# Panel_Interface.net
KiCad netlist of a schematic drawn in Altium Designer
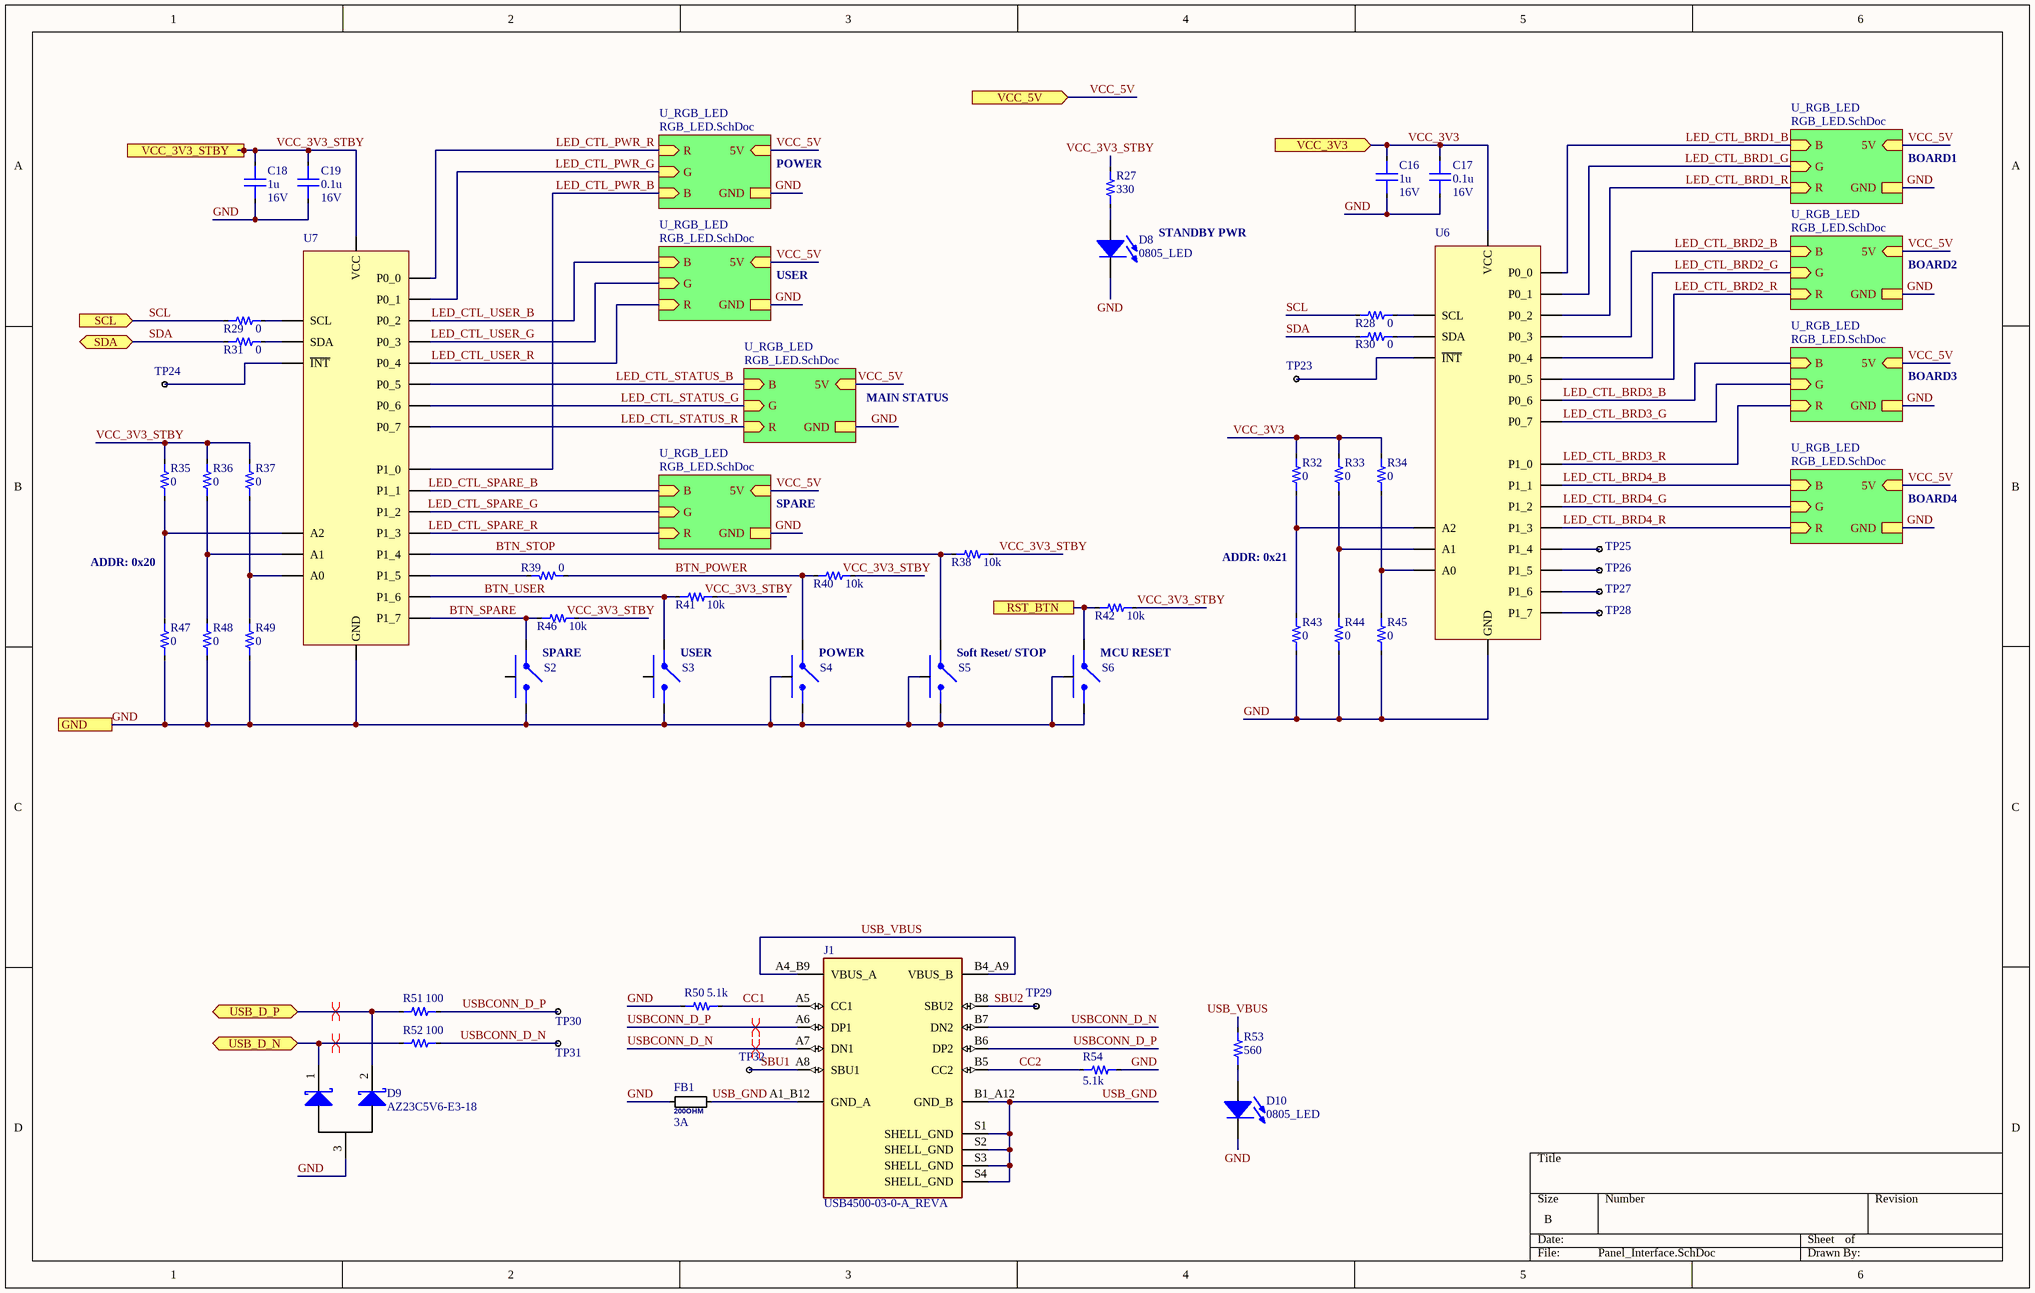
[diagram p0: Panel_Interface.SchDoc]

(export (version "E")
  (design (tool "Eeschema 10.0.6"))
  (components
    (comp (ref "C16")
      (value "1u")
      (footprint "0603_CAP")
      (fields (field (name "VOLTAGE") "16V") (field (name "Comment") "Capacitor"))
      (libsource (lib "Capacitors") (part "Capacitor"))
    )
    (comp (ref "C17")
      (value "0.1u")
      (footprint "0603_CAP")
      (fields (field (name "VOLTAGE") "16V") (field (name "Comment") "Capacitor"))
      (libsource (lib "Capacitors") (part "Capacitor"))
    )
    (comp (ref "C18")
      (value "1u")
      (footprint "0603_CAP")
      (fields (field (name "VOLTAGE") "16V") (field (name "Comment") "Capacitor"))
      (libsource (lib "Capacitors") (part "Capacitor"))
    )
    (comp (ref "C19")
      (value "0.1u")
      (footprint "0603_CAP")
      (fields (field (name "VOLTAGE") "16V") (field (name "Comment") "Capacitor"))
      (libsource (lib "Capacitors") (part "Capacitor"))
    )
    (comp (ref "D8")
      (value "0805_LED")
      (footprint "0805_LED")
      (description "Generic 0805 LED")
      (libsource (lib "Diodes") (part "0805_LED"))
    )
    (comp (ref "D9")
      (value "AZ23C5V6-E3-18")
      (footprint "SOT23-3")
      (description "Zener Diode Array 1 Pair Common Anode 5.6 V 300 mW ±7% SOT-23-3")
      (libsource (lib "Diodes") (part "AZ23C5V6-E3-18"))
    )
    (comp (ref "D10")
      (value "0805_LED")
      (footprint "0805_LED")
      (description "Generic 0805 LED")
      (libsource (lib "Diodes") (part "0805_LED"))
    )
    (comp (ref "FB1")
      (value "*")
      (footprint "0805_Ferrite")
      (fields (field (name "=Z@100MHZ") "200OHM") (field (name "IMAX") "3A"))
      (libsource (lib "Magnetic") (part "ChipFerrite"))
    )
    (comp (ref "J1")
      (value "USB4500-03-0-A_REVA")
      (footprint "GCT_USB4500-03-0-A_REVA")
      (description "Type C USB 2.0 Connector")
      (fields (field (name "MP") "USB4500-03-0-A") (field (name "MF") "Global Connector Technology"))
      (libsource (lib "Connectors") (part "USB4500-03-0-A_REVA"))
    )
    (comp (ref "R27")
      (value "330")
      (footprint "0603_RES")
      (fields (field (name "Comment") "Resistor"))
      (libsource (lib "Resistors") (part "Resistor"))
    )
    (comp (ref "R28")
      (value "0")
      (footprint "0603_RES")
      (fields (field (name "Comment") "Resistor"))
      (libsource (lib "Resistors") (part "Resistor"))
    )
    (comp (ref "R29")
      (value "0")
      (footprint "0603_RES")
      (fields (field (name "Comment") "Resistor"))
      (libsource (lib "Resistors") (part "Resistor"))
    )
    (comp (ref "R30")
      (value "0")
      (footprint "0603_RES")
      (fields (field (name "Comment") "Resistor"))
      (libsource (lib "Resistors") (part "Resistor"))
    )
    (comp (ref "R31")
      (value "0")
      (footprint "0603_RES")
      (fields (field (name "Comment") "Resistor"))
      (libsource (lib "Resistors") (part "Resistor"))
    )
    (comp (ref "R32")
      (value "0")
      (footprint "0603_RES")
      (fields (field (name "Comment") "Resistor"))
      (libsource (lib "Resistors") (part "Resistor"))
    )
    (comp (ref "R33")
      (value "0")
      (footprint "0603_RES")
      (fields (field (name "Comment") "Resistor"))
      (libsource (lib "Resistors") (part "Resistor"))
    )
    (comp (ref "R34")
      (value "0")
      (footprint "0603_RES")
      (fields (field (name "Comment") "Resistor"))
      (libsource (lib "Resistors") (part "Resistor"))
    )
    (comp (ref "R35")
      (value "0")
      (footprint "0603_RES")
      (fields (field (name "Comment") "Resistor"))
      (libsource (lib "Resistors") (part "Resistor"))
    )
    (comp (ref "R36")
      (value "0")
      (footprint "0603_RES")
      (fields (field (name "Comment") "Resistor"))
      (libsource (lib "Resistors") (part "Resistor"))
    )
    (comp (ref "R37")
      (value "0")
      (footprint "0603_RES")
      (fields (field (name "Comment") "Resistor"))
      (libsource (lib "Resistors") (part "Resistor"))
    )
    (comp (ref "R38")
      (value "10k")
      (footprint "0603_RES")
      (fields (field (name "Comment") "Resistor"))
      (libsource (lib "Resistors") (part "Resistor"))
    )
    (comp (ref "R39")
      (value "0")
      (footprint "0603_RES")
      (fields (field (name "Comment") "Resistor"))
      (libsource (lib "Resistors") (part "Resistor"))
    )
    (comp (ref "R40")
      (value "10k")
      (footprint "0603_RES")
      (fields (field (name "Comment") "Resistor"))
      (libsource (lib "Resistors") (part "Resistor"))
    )
    (comp (ref "R41")
      (value "10k")
      (footprint "0603_RES")
      (fields (field (name "Comment") "Resistor"))
      (libsource (lib "Resistors") (part "Resistor"))
    )
    (comp (ref "R42")
      (value "10k")
      (footprint "0603_RES")
      (fields (field (name "Comment") "Resistor"))
      (libsource (lib "Resistors") (part "Resistor"))
    )
    (comp (ref "R43")
      (value "0")
      (footprint "0603_RES")
      (fields (field (name "Comment") "Resistor"))
      (libsource (lib "Resistors") (part "Resistor"))
    )
    (comp (ref "R44")
      (value "0")
      (footprint "0603_RES")
      (fields (field (name "Comment") "Resistor"))
      (libsource (lib "Resistors") (part "Resistor"))
    )
    (comp (ref "R45")
      (value "0")
      (footprint "0603_RES")
      (fields (field (name "Comment") "Resistor"))
      (libsource (lib "Resistors") (part "Resistor"))
    )
    (comp (ref "R46")
      (value "10k")
      (footprint "0603_RES")
      (fields (field (name "Comment") "Resistor"))
      (libsource (lib "Resistors") (part "Resistor"))
    )
    (comp (ref "R47")
      (value "0")
      (footprint "0603_RES")
      (fields (field (name "Comment") "Resistor"))
      (libsource (lib "Resistors") (part "Resistor"))
    )
    (comp (ref "R48")
      (value "0")
      (footprint "0603_RES")
      (fields (field (name "Comment") "Resistor"))
      (libsource (lib "Resistors") (part "Resistor"))
    )
    (comp (ref "R49")
      (value "0")
      (footprint "0603_RES")
      (fields (field (name "Comment") "Resistor"))
      (libsource (lib "Resistors") (part "Resistor"))
    )
    (comp (ref "R50")
      (value "5.1k")
      (footprint "0603_RES")
      (fields (field (name "Comment") "Resistor"))
      (libsource (lib "Resistors") (part "Resistor"))
    )
    (comp (ref "R51")
      (value "100")
      (footprint "0603_RES")
      (fields (field (name "Comment") "Resistor"))
      (libsource (lib "Resistors") (part "Resistor"))
    )
    (comp (ref "R52")
      (value "100")
      (footprint "0603_RES")
      (fields (field (name "Comment") "Resistor"))
      (libsource (lib "Resistors") (part "Resistor"))
    )
    (comp (ref "R53")
      (value "560")
      (footprint "0603_RES")
      (fields (field (name "Comment") "Resistor"))
      (libsource (lib "Resistors") (part "Resistor"))
    )
    (comp (ref "R54")
      (value "5.1k")
      (footprint "0603_RES")
      (fields (field (name "Comment") "Resistor"))
      (libsource (lib "Resistors") (part "Resistor"))
    )
    (comp (ref "S2")
      (value "PTS645V")
      (footprint "PTS645V")
      (description "Tactile Switch SPST-NO Side Actuated Surface Mount, Right Angle")
      (libsource (lib "ElectroMechanical") (part "PTS645V"))
    )
    (comp (ref "S3")
      (value "PTS645V")
      (footprint "PTS645V")
      (description "Tactile Switch SPST-NO Side Actuated Surface Mount, Right Angle")
      (libsource (lib "ElectroMechanical") (part "PTS645V"))
    )
    (comp (ref "S4")
      (value "PTS645V")
      (footprint "PTS645V")
      (description "Tactile Switch SPST-NO Side Actuated Surface Mount, Right Angle")
      (libsource (lib "ElectroMechanical") (part "PTS645V"))
    )
    (comp (ref "S5")
      (value "PTS645V")
      (footprint "PTS645V")
      (description "Tactile Switch SPST-NO Side Actuated Surface Mount, Right Angle")
      (libsource (lib "ElectroMechanical") (part "PTS645V"))
    )
    (comp (ref "S6")
      (value "PTS645V")
      (footprint "PTS645V")
      (description "Tactile Switch SPST-NO Side Actuated Surface Mount, Right Angle")
      (libsource (lib "ElectroMechanical") (part "PTS645V"))
    )
    (comp (ref "TP23")
      (value "1mm Testpoint")
      (footprint "1mm_testpoint")
      (description "1mm test point")
      (libsource (lib "Connectors") (part "1mm Testpoint"))
    )
    (comp (ref "TP24")
      (value "1mm Testpoint")
      (footprint "1mm_testpoint")
      (description "1mm test point")
      (libsource (lib "Connectors") (part "1mm Testpoint"))
    )
    (comp (ref "TP25")
      (value "1mm Testpoint")
      (footprint "1mm_testpoint")
      (description "1mm test point")
      (libsource (lib "Connectors") (part "1mm Testpoint"))
    )
    (comp (ref "TP26")
      (value "1mm Testpoint")
      (footprint "1mm_testpoint")
      (description "1mm test point")
      (libsource (lib "Connectors") (part "1mm Testpoint"))
    )
    (comp (ref "TP27")
      (value "1mm Testpoint")
      (footprint "1mm_testpoint")
      (description "1mm test point")
      (libsource (lib "Connectors") (part "1mm Testpoint"))
    )
    (comp (ref "TP28")
      (value "1mm Testpoint")
      (footprint "1mm_testpoint")
      (description "1mm test point")
      (libsource (lib "Connectors") (part "1mm Testpoint"))
    )
    (comp (ref "TP29")
      (value "1mm Testpoint")
      (footprint "1mm_testpoint")
      (description "1mm test point")
      (libsource (lib "Connectors") (part "1mm Testpoint"))
    )
    (comp (ref "TP30")
      (value "1mm Testpoint")
      (footprint "1mm_testpoint")
      (description "1mm test point")
      (libsource (lib "Connectors") (part "1mm Testpoint"))
    )
    (comp (ref "TP31")
      (value "1mm Testpoint")
      (footprint "1mm_testpoint")
      (description "1mm test point")
      (libsource (lib "Connectors") (part "1mm Testpoint"))
    )
    (comp (ref "TP32")
      (value "1mm Testpoint")
      (footprint "1mm_testpoint")
      (description "1mm test point")
      (libsource (lib "Connectors") (part "1mm Testpoint"))
    )
    (comp (ref "U6")
      (value "NCA9535-Q100")
      (footprint "TSSOP-24. 4.4mm width")
      (description "I/O Expander 16 I2C, SMBus 400 kHz 24-TSSOP")
      (libsource (lib "Digital_IC") (part "NCA9535-Q100"))
    )
    (comp (ref "U7")
      (value "NCA9535-Q100")
      (footprint "TSSOP-24. 4.4mm width")
      (description "I/O Expander 16 I2C, SMBus 400 kHz 24-TSSOP")
      (libsource (lib "Digital_IC") (part "NCA9535-Q100"))
    )
  )
  (nets
    (net (code "1") (name "/BTN_POWER") (class "Default")
      (node (ref "R39") (pin "1") (pinfunction "1_1") (pintype "passive"))
      (node (ref "R40") (pin "1") (pinfunction "1_1") (pintype "passive"))
      (node (ref "S4") (pin "1") (pinfunction "1_1") (pintype "passive"))
    )
    (net (code "2") (name "/BTN_SPARE") (class "Default")
      (node (ref "R46") (pin "1") (pinfunction "1_1") (pintype "passive"))
      (node (ref "S2") (pin "1") (pinfunction "1_1") (pintype "passive"))
      (node (ref "U7") (pin "20") (pinfunction "P1_7_20") (pintype "passive"))
    )
    (net (code "3") (name "/BTN_STOP") (class "Default")
      (node (ref "R38") (pin "1") (pinfunction "1_1") (pintype "passive"))
      (node (ref "S5") (pin "1") (pinfunction "1_1") (pintype "passive"))
      (node (ref "U7") (pin "17") (pinfunction "P1_4_17") (pintype "passive"))
    )
    (net (code "4") (name "/BTN_USER") (class "Default")
      (node (ref "R41") (pin "1") (pinfunction "1_1") (pintype "passive"))
      (node (ref "S3") (pin "1") (pinfunction "1_1") (pintype "passive"))
      (node (ref "U7") (pin "19") (pinfunction "P1_6_19") (pintype "passive"))
    )
    (net (code "5") (name "/CC1") (class "Default")
      (node (ref "J1") (pin "A5") (pinfunction "CC1_A5") (pintype "bidirectional"))
      (node (ref "R50") (pin "2") (pinfunction "2_2") (pintype "passive"))
    )
    (net (code "6") (name "/CC2") (class "Default")
      (node (ref "J1") (pin "B5") (pinfunction "CC2_B5") (pintype "bidirectional"))
      (node (ref "R54") (pin "1") (pinfunction "1_1") (pintype "passive"))
    )
    (net (code "7") (name "/GND") (class "Default")
      (node (ref "C16") (pin "1") (pinfunction "1_1") (pintype "passive"))
      (node (ref "C17") (pin "1") (pinfunction "1_1") (pintype "passive"))
      (node (ref "C18") (pin "1") (pinfunction "1_1") (pintype "passive"))
      (node (ref "C19") (pin "1") (pinfunction "1_1") (pintype "passive"))
      (node (ref "D10") (pin "2") (pinfunction "K_2") (pintype "passive"))
      (node (ref "D8") (pin "2") (pinfunction "K_2") (pintype "passive"))
      (node (ref "D9") (pin "3") (pinfunction "3_3") (pintype "passive"))
      (node (ref "FB1") (pin "1") (pinfunction "1_1") (pintype "passive"))
      (node (ref "R43") (pin "1") (pinfunction "1_1") (pintype "passive"))
      (node (ref "R44") (pin "1") (pinfunction "1_1") (pintype "passive"))
      (node (ref "R45") (pin "1") (pinfunction "1_1") (pintype "passive"))
      (node (ref "R47") (pin "1") (pinfunction "1_1") (pintype "passive"))
      (node (ref "R48") (pin "1") (pinfunction "1_1") (pintype "passive"))
      (node (ref "R49") (pin "1") (pinfunction "1_1") (pintype "passive"))
      (node (ref "R50") (pin "1") (pinfunction "1_1") (pintype "passive"))
      (node (ref "R54") (pin "2") (pinfunction "2_2") (pintype "passive"))
      (node (ref "S2") (pin "2") (pinfunction "2_2") (pintype "passive"))
      (node (ref "S3") (pin "2") (pinfunction "2_2") (pintype "passive"))
      (node (ref "S4") (pin "2") (pinfunction "2_2") (pintype "passive"))
      (node (ref "S4") (pin "TAB") (pinfunction "TAB_TAB") (pintype "passive"))
      (node (ref "S5") (pin "2") (pinfunction "2_2") (pintype "passive"))
      (node (ref "S5") (pin "TAB") (pinfunction "TAB_TAB") (pintype "passive"))
      (node (ref "S6") (pin "2") (pinfunction "2_2") (pintype "passive"))
      (node (ref "S6") (pin "TAB") (pinfunction "TAB_TAB") (pintype "passive"))
      (node (ref "U6") (pin "12") (pinfunction "GND_12") (pintype "passive"))
      (node (ref "U7") (pin "12") (pinfunction "GND_12") (pintype "passive"))
    )
    (net (code "8") (name "/LED_CTL_BRD1_B") (class "Default")
      (node (ref "U6") (pin "4") (pinfunction "P0_0_4") (pintype "passive"))
    )
    (net (code "9") (name "/LED_CTL_BRD1_G") (class "Default")
      (node (ref "U6") (pin "5") (pinfunction "P0_1_5") (pintype "passive"))
    )
    (net (code "10") (name "/LED_CTL_BRD1_R") (class "Default")
      (node (ref "U6") (pin "6") (pinfunction "P0_2_6") (pintype "passive"))
    )
    (net (code "11") (name "/LED_CTL_BRD2_B") (class "Default")
      (node (ref "U6") (pin "7") (pinfunction "P0_3_7") (pintype "passive"))
    )
    (net (code "12") (name "/LED_CTL_BRD2_G") (class "Default")
      (node (ref "U6") (pin "8") (pinfunction "P0_4_8") (pintype "passive"))
    )
    (net (code "13") (name "/LED_CTL_BRD2_R") (class "Default")
      (node (ref "U6") (pin "9") (pinfunction "P0_5_9") (pintype "passive"))
    )
    (net (code "14") (name "/LED_CTL_BRD3_B") (class "Default")
      (node (ref "U6") (pin "10") (pinfunction "P0_6_10") (pintype "passive"))
    )
    (net (code "15") (name "/LED_CTL_BRD3_G") (class "Default")
      (node (ref "U6") (pin "11") (pinfunction "P0_7_11") (pintype "passive"))
    )
    (net (code "16") (name "/LED_CTL_BRD3_R") (class "Default")
      (node (ref "U6") (pin "13") (pinfunction "P1_0_13") (pintype "passive"))
    )
    (net (code "17") (name "/LED_CTL_BRD4_B") (class "Default")
      (node (ref "U6") (pin "14") (pinfunction "P1_1_14") (pintype "passive"))
    )
    (net (code "18") (name "/LED_CTL_BRD4_G") (class "Default")
      (node (ref "U6") (pin "15") (pinfunction "P1_2_15") (pintype "passive"))
    )
    (net (code "19") (name "/LED_CTL_BRD4_R") (class "Default")
      (node (ref "U6") (pin "16") (pinfunction "P1_3_16") (pintype "passive"))
    )
    (net (code "20") (name "/LED_CTL_PWR_B") (class "Default")
      (node (ref "U7") (pin "13") (pinfunction "P1_0_13") (pintype "passive"))
    )
    (net (code "21") (name "/LED_CTL_PWR_G") (class "Default")
      (node (ref "U7") (pin "5") (pinfunction "P0_1_5") (pintype "passive"))
    )
    (net (code "22") (name "/LED_CTL_PWR_R") (class "Default")
      (node (ref "U7") (pin "4") (pinfunction "P0_0_4") (pintype "passive"))
    )
    (net (code "23") (name "/LED_CTL_SPARE_B") (class "Default")
      (node (ref "U7") (pin "14") (pinfunction "P1_1_14") (pintype "passive"))
    )
    (net (code "24") (name "/LED_CTL_SPARE_G") (class "Default")
      (node (ref "U7") (pin "15") (pinfunction "P1_2_15") (pintype "passive"))
    )
    (net (code "25") (name "/LED_CTL_SPARE_R") (class "Default")
      (node (ref "U7") (pin "16") (pinfunction "P1_3_16") (pintype "passive"))
    )
    (net (code "26") (name "/LED_CTL_STATUS_B") (class "Default")
      (node (ref "U7") (pin "9") (pinfunction "P0_5_9") (pintype "passive"))
    )
    (net (code "27") (name "/LED_CTL_STATUS_G") (class "Default")
      (node (ref "U7") (pin "10") (pinfunction "P0_6_10") (pintype "passive"))
    )
    (net (code "28") (name "/LED_CTL_STATUS_R") (class "Default")
      (node (ref "U7") (pin "11") (pinfunction "P0_7_11") (pintype "passive"))
    )
    (net (code "29") (name "/LED_CTL_USER_B") (class "Default")
      (node (ref "U7") (pin "6") (pinfunction "P0_2_6") (pintype "passive"))
    )
    (net (code "30") (name "/LED_CTL_USER_G") (class "Default")
      (node (ref "U7") (pin "7") (pinfunction "P0_3_7") (pintype "passive"))
    )
    (net (code "31") (name "/LED_CTL_USER_R") (class "Default")
      (node (ref "U7") (pin "8") (pinfunction "P0_4_8") (pintype "passive"))
    )
    (net (code "32") (name "/RST_BTN") (class "Default")
      (node (ref "R42") (pin "1") (pinfunction "1_1") (pintype "passive"))
      (node (ref "S6") (pin "1") (pinfunction "1_1") (pintype "passive"))
    )
    (net (code "33") (name "/SBU1") (class "Default")
      (node (ref "J1") (pin "A8") (pinfunction "SBU1_A8") (pintype "bidirectional"))
      (node (ref "TP32") (pin "1") (pintype "passive"))
    )
    (net (code "34") (name "/SBU2") (class "Default")
      (node (ref "J1") (pin "B8") (pinfunction "SBU2_B8") (pintype "bidirectional"))
      (node (ref "TP29") (pin "1") (pintype "passive"))
    )
    (net (code "35") (name "/SCL") (class "Default")
      (node (ref "R28") (pin "1") (pinfunction "1_1") (pintype "passive"))
      (node (ref "R29") (pin "1") (pinfunction "1_1") (pintype "passive"))
    )
    (net (code "36") (name "/SDA") (class "Default")
      (node (ref "R30") (pin "1") (pinfunction "1_1") (pintype "passive"))
      (node (ref "R31") (pin "1") (pinfunction "1_1") (pintype "passive"))
    )
    (net (code "37") (name "/USBCONN_D_N") (class "Default")
      (node (ref "J1") (pin "A7") (pinfunction "DN1_A7") (pintype "bidirectional"))
      (node (ref "J1") (pin "B7") (pinfunction "DN2_B7") (pintype "bidirectional"))
      (node (ref "R52") (pin "2") (pinfunction "2_2") (pintype "passive"))
      (node (ref "TP31") (pin "1") (pintype "passive"))
    )
    (net (code "38") (name "/USBCONN_D_P") (class "Default")
      (node (ref "J1") (pin "A6") (pinfunction "DP1_A6") (pintype "bidirectional"))
      (node (ref "J1") (pin "B6") (pinfunction "DP2_B6") (pintype "bidirectional"))
      (node (ref "R51") (pin "2") (pinfunction "2_2") (pintype "passive"))
      (node (ref "TP30") (pin "1") (pintype "passive"))
    )
    (net (code "39") (name "/USB_D_N") (class "Default")
      (node (ref "D9") (pin "1") (pinfunction "1_1") (pintype "passive"))
      (node (ref "R52") (pin "1") (pinfunction "1_1") (pintype "passive"))
    )
    (net (code "40") (name "/USB_D_P") (class "Default")
      (node (ref "D9") (pin "2") (pinfunction "2_2") (pintype "passive"))
      (node (ref "R51") (pin "1") (pinfunction "1_1") (pintype "passive"))
    )
    (net (code "41") (name "/USB_GND") (class "Default")
      (node (ref "FB1") (pin "2") (pinfunction "2_2") (pintype "passive"))
      (node (ref "J1") (pin "A1_B12") (pinfunction "GND_A_A1_B12") (pintype "power_in"))
      (node (ref "J1") (pin "B1_A12") (pinfunction "GND_B_B1_A12") (pintype "power_in"))
      (node (ref "J1") (pin "S1") (pinfunction "SHELL_GND_S1") (pintype "power_in"))
      (node (ref "J1") (pin "S2") (pinfunction "SHELL_GND_S2") (pintype "power_in"))
      (node (ref "J1") (pin "S3") (pinfunction "SHELL_GND_S3") (pintype "power_in"))
      (node (ref "J1") (pin "S4") (pinfunction "SHELL_GND_S4") (pintype "power_in"))
    )
    (net (code "42") (name "/USB_VBUS") (class "Default")
      (node (ref "J1") (pin "A4_B9") (pinfunction "VBUS_A_A4_B9") (pintype "power_in"))
      (node (ref "J1") (pin "B4_A9") (pinfunction "VBUS_B_B4_A9") (pintype "power_in"))
      (node (ref "R53") (pin "2") (pinfunction "2_2") (pintype "passive"))
    )
    (net (code "43") (name "/VCC_3V3") (class "Default")
      (node (ref "C16") (pin "2") (pinfunction "2_2") (pintype "passive"))
      (node (ref "C17") (pin "2") (pinfunction "2_2") (pintype "passive"))
      (node (ref "R32") (pin "2") (pinfunction "2_2") (pintype "passive"))
      (node (ref "R33") (pin "2") (pinfunction "2_2") (pintype "passive"))
      (node (ref "R34") (pin "2") (pinfunction "2_2") (pintype "passive"))
      (node (ref "U6") (pin "24") (pinfunction "VCC_24") (pintype "passive"))
    )
    (net (code "44") (name "/VCC_3V3_STBY") (class "Default")
      (node (ref "C18") (pin "2") (pinfunction "2_2") (pintype "passive"))
      (node (ref "C19") (pin "2") (pinfunction "2_2") (pintype "passive"))
      (node (ref "R27") (pin "2") (pinfunction "2_2") (pintype "passive"))
      (node (ref "R35") (pin "2") (pinfunction "2_2") (pintype "passive"))
      (node (ref "R36") (pin "2") (pinfunction "2_2") (pintype "passive"))
      (node (ref "R37") (pin "2") (pinfunction "2_2") (pintype "passive"))
      (node (ref "R38") (pin "2") (pinfunction "2_2") (pintype "passive"))
      (node (ref "R40") (pin "2") (pinfunction "2_2") (pintype "passive"))
      (node (ref "R41") (pin "2") (pinfunction "2_2") (pintype "passive"))
      (node (ref "R42") (pin "2") (pinfunction "2_2") (pintype "passive"))
      (node (ref "R46") (pin "2") (pinfunction "2_2") (pintype "passive"))
      (node (ref "U7") (pin "24") (pinfunction "VCC_24") (pintype "passive"))
    )
    (net (code "46") (name "Net-(D8-A)") (class "Default")
      (node (ref "D8") (pin "1") (pinfunction "A_1") (pintype "passive"))
      (node (ref "R27") (pin "1") (pinfunction "1_1") (pintype "passive"))
    )
    (net (code "47") (name "Net-(D10-A)") (class "Default")
      (node (ref "D10") (pin "1") (pinfunction "A_1") (pintype "passive"))
      (node (ref "R53") (pin "1") (pinfunction "1_1") (pintype "passive"))
    )
    (net (code "48") (name "Net-(U6-A0)") (class "Default")
      (node (ref "R34") (pin "1") (pinfunction "1_1") (pintype "passive"))
      (node (ref "R45") (pin "2") (pinfunction "2_2") (pintype "passive"))
      (node (ref "U6") (pin "21") (pinfunction "A0_21") (pintype "passive"))
    )
    (net (code "49") (name "Net-(U6-A1)") (class "Default")
      (node (ref "R33") (pin "1") (pinfunction "1_1") (pintype "passive"))
      (node (ref "R44") (pin "2") (pinfunction "2_2") (pintype "passive"))
      (node (ref "U6") (pin "2") (pinfunction "A1_2") (pintype "passive"))
    )
    (net (code "50") (name "Net-(U6-A2)") (class "Default")
      (node (ref "R32") (pin "1") (pinfunction "1_1") (pintype "passive"))
      (node (ref "R43") (pin "2") (pinfunction "2_2") (pintype "passive"))
      (node (ref "U6") (pin "3") (pinfunction "A2_3") (pintype "passive"))
    )
    (net (code "51") (name "Net-(U6-P1_4)") (class "Default")
      (node (ref "TP25") (pin "1") (pintype "passive"))
      (node (ref "U6") (pin "17") (pinfunction "P1_4_17") (pintype "passive"))
    )
    (net (code "52") (name "Net-(U6-P1_5)") (class "Default")
      (node (ref "TP26") (pin "1") (pintype "passive"))
      (node (ref "U6") (pin "18") (pinfunction "P1_5_18") (pintype "passive"))
    )
    (net (code "53") (name "Net-(U6-P1_6)") (class "Default")
      (node (ref "TP27") (pin "1") (pintype "passive"))
      (node (ref "U6") (pin "19") (pinfunction "P1_6_19") (pintype "passive"))
    )
    (net (code "54") (name "Net-(U6-P1_7)") (class "Default")
      (node (ref "TP28") (pin "1") (pintype "passive"))
      (node (ref "U6") (pin "20") (pinfunction "P1_7_20") (pintype "passive"))
    )
    (net (code "55") (name "Net-(U6-SCL)") (class "Default")
      (node (ref "R28") (pin "2") (pinfunction "2_2") (pintype "passive"))
      (node (ref "U6") (pin "22") (pinfunction "SCL_22") (pintype "passive"))
    )
    (net (code "56") (name "Net-(U6-SDA)") (class "Default")
      (node (ref "R30") (pin "2") (pinfunction "2_2") (pintype "passive"))
      (node (ref "U6") (pin "23") (pinfunction "SDA_23") (pintype "passive"))
    )
    (net (code "57") (name "Net-(U6-~{INT})") (class "Default")
      (node (ref "TP23") (pin "1") (pintype "passive"))
      (node (ref "U6") (pin "1") (pinfunction "~{INT}_1") (pintype "passive"))
    )
    (net (code "58") (name "Net-(U7-A0)") (class "Default")
      (node (ref "R37") (pin "1") (pinfunction "1_1") (pintype "passive"))
      (node (ref "R49") (pin "2") (pinfunction "2_2") (pintype "passive"))
      (node (ref "U7") (pin "21") (pinfunction "A0_21") (pintype "passive"))
    )
    (net (code "59") (name "Net-(U7-A1)") (class "Default")
      (node (ref "R36") (pin "1") (pinfunction "1_1") (pintype "passive"))
      (node (ref "R48") (pin "2") (pinfunction "2_2") (pintype "passive"))
      (node (ref "U7") (pin "2") (pinfunction "A1_2") (pintype "passive"))
    )
    (net (code "60") (name "Net-(U7-A2)") (class "Default")
      (node (ref "R35") (pin "1") (pinfunction "1_1") (pintype "passive"))
      (node (ref "R47") (pin "2") (pinfunction "2_2") (pintype "passive"))
      (node (ref "U7") (pin "3") (pinfunction "A2_3") (pintype "passive"))
    )
    (net (code "61") (name "Net-(U7-P1_5)") (class "Default")
      (node (ref "R39") (pin "2") (pinfunction "2_2") (pintype "passive"))
      (node (ref "U7") (pin "18") (pinfunction "P1_5_18") (pintype "passive"))
    )
    (net (code "62") (name "Net-(U7-SCL)") (class "Default")
      (node (ref "R29") (pin "2") (pinfunction "2_2") (pintype "passive"))
      (node (ref "U7") (pin "22") (pinfunction "SCL_22") (pintype "passive"))
    )
    (net (code "63") (name "Net-(U7-SDA)") (class "Default")
      (node (ref "R31") (pin "2") (pinfunction "2_2") (pintype "passive"))
      (node (ref "U7") (pin "23") (pinfunction "SDA_23") (pintype "passive"))
    )
    (net (code "64") (name "Net-(U7-~{INT})") (class "Default")
      (node (ref "TP24") (pin "1") (pintype "passive"))
      (node (ref "U7") (pin "1") (pinfunction "~{INT}_1") (pintype "passive"))
    )
    (net (code "65") (name "unconnected-(S2-PadTAB)") (class "Default")
      (node (ref "S2") (pin "TAB") (pinfunction "TAB_TAB") (pintype "passive"))
    )
    (net (code "66") (name "unconnected-(S3-PadTAB)") (class "Default")
      (node (ref "S3") (pin "TAB") (pinfunction "TAB_TAB") (pintype "passive"))
    )
  )
)
